# design4A.net
KiCad netlist of a schematic drawn in EAGLE
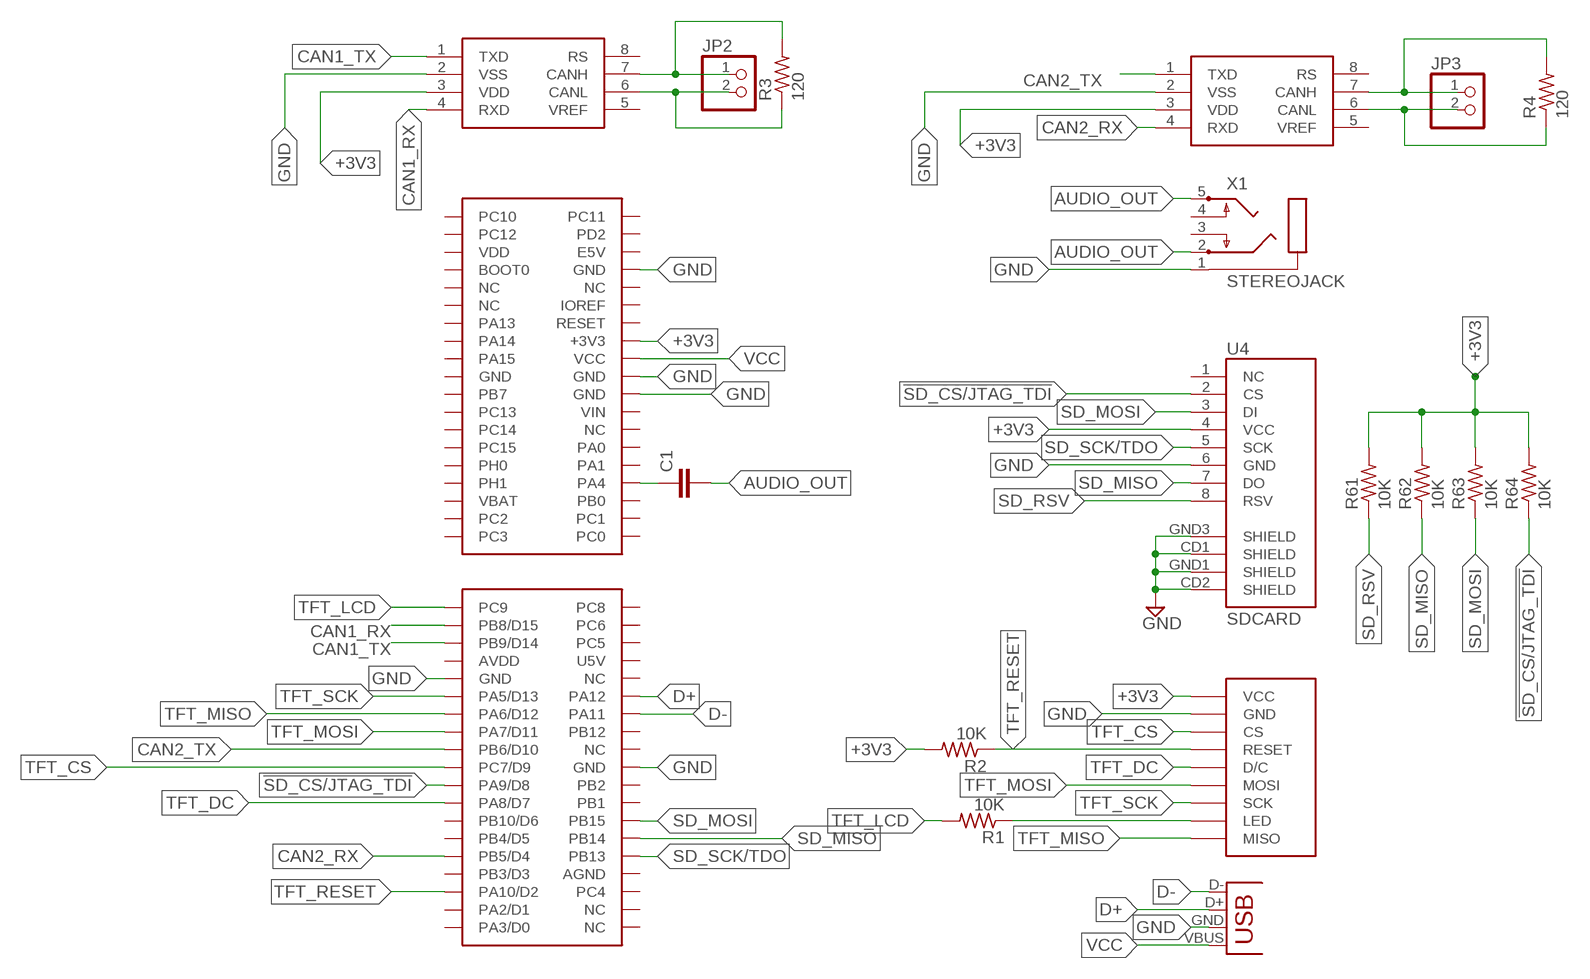
[diagram p0: schematic, sheet 1]

(export (version "E")
  (design (tool "Eeschema 10.0.6"))
  (components
    (comp (ref "C1")
      (value "CAP1206")
      (footprint "eagle-import:1206")
      (libsource (lib "eagle-import") (part "CAP1206"))
    )
    (comp (ref "J1")
      (value "SPI_TFT_DISPLAY")
      (footprint "eagle-import:SPI_DISPLAY")
      (libsource (lib "eagle-import") (part "SPI_TFT_DISPLAY"))
    )
    (comp (ref "JP1")
      (value "USB-A-H")
      (footprint "eagle-import:USB-A-H")
      (libsource (lib "eagle-import") (part "USB-A-H"))
    )
    (comp (ref "JP2")
      (value "HEADER-1X2")
      (footprint "eagle-import:1X02_OVAL")
      (libsource (lib "eagle-import") (part "HEADER-1X2"))
    )
    (comp (ref "JP3")
      (value "HEADER-1X2")
      (footprint "eagle-import:1X02_OVAL")
      (libsource (lib "eagle-import") (part "HEADER-1X2"))
    )
    (comp (ref "R1")
      (value "10K")
      (footprint "eagle-import:RLC_0603@1")
      (fields (field (name "MPN") "RMCF0603JT10K0"))
      (libsource (lib "eagle-import") (part "RESISTORRLC_0603"))
    )
    (comp (ref "R2")
      (value "10K")
      (footprint "eagle-import:RLC_0603@1")
      (fields (field (name "MPN") "RMCF0603JT10K0"))
      (libsource (lib "eagle-import") (part "RESISTORRLC_0603"))
    )
    (comp (ref "R3")
      (value "120")
      (footprint "eagle-import:RLC_0603@1")
      (fields (field (name "MPN") "RMCF0603JT10K0"))
      (libsource (lib "eagle-import") (part "RESISTORRLC_0603"))
    )
    (comp (ref "R4")
      (value "120")
      (footprint "eagle-import:RLC_0603@1")
      (fields (field (name "MPN") "RMCF0603JT10K0"))
      (libsource (lib "eagle-import") (part "RESISTORRLC_0603"))
    )
    (comp (ref "R61")
      (value "10K")
      (footprint "eagle-import:RLC_0603@1")
      (fields (field (name "MPN") "RMCF0603JT10K0"))
      (libsource (lib "eagle-import") (part "RESISTORRLC_0603"))
    )
    (comp (ref "R62")
      (value "10K")
      (footprint "eagle-import:RLC_0603@1")
      (fields (field (name "MPN") "RMCF0603JT10K0"))
      (libsource (lib "eagle-import") (part "RESISTORRLC_0603"))
    )
    (comp (ref "R63")
      (value "10K")
      (footprint "eagle-import:RLC_0603@1")
      (fields (field (name "MPN") "RMCF0603JT10K0"))
      (libsource (lib "eagle-import") (part "RESISTORRLC_0603"))
    )
    (comp (ref "R64")
      (value "10K")
      (footprint "eagle-import:RLC_0603@1")
      (fields (field (name "MPN") "RMCF0603JT10K0"))
      (libsource (lib "eagle-import") (part "RESISTORRLC_0603"))
    )
    (comp (ref "U$1")
      (value "MOPHOMOPHO_466RE")
      (footprint "eagle-import:MOPHO")
      (libsource (lib "eagle-import") (part "MOPHOMOPHO_466RE"))
    )
    (comp (ref "U1")
      (value "MCP2551")
      (footprint "eagle-import:SO08")
      (libsource (lib "eagle-import") (part "MCP2551"))
    )
    (comp (ref "U2")
      (value "MCP2551")
      (footprint "eagle-import:SO08")
      (libsource (lib "eagle-import") (part "MCP2551"))
    )
    (comp (ref "U4")
      (value "SDCARD")
      (footprint "eagle-import:MICRO-SD-SOCKET-PP")
      (libsource (lib "eagle-import") (part "USD-SOCKETNEW"))
    )
    (comp (ref "X1")
      (value "STEREOJACK")
      (footprint "eagle-import:STX3100")
      (libsource (lib "eagle-import") (part "STEREOJACK"))
    )
  )
  (nets
    (net (code "1") (name "+3V3") (class "Default")
      (node (ref "J1") (pin "VCC") (pinfunction "VCC_VCC") (pintype "power_in"))
      (node (ref "R2") (pin "2") (pinfunction "2_2") (pintype "passive"))
      (node (ref "R61") (pin "2") (pinfunction "2_2") (pintype "passive"))
      (node (ref "R62") (pin "2") (pinfunction "2_2") (pintype "passive"))
      (node (ref "R63") (pin "2") (pinfunction "2_2") (pintype "passive"))
      (node (ref "R64") (pin "2") (pinfunction "2_2") (pintype "passive"))
      (node (ref "U$1") (pin "P$16") (pinfunction "+3V3_P$16") (pintype "power_in"))
      (node (ref "U1") (pin "3") (pinfunction "VDD_3") (pintype "bidirectional"))
      (node (ref "U2") (pin "3") (pinfunction "VDD_3") (pintype "bidirectional"))
      (node (ref "U4") (pin "4") (pinfunction "VCC_4") (pintype "bidirectional"))
    )
    (net (code "2") (name "/AVDD") (class "Default")
      (node (ref "U$1") (pin "P$45") (pinfunction "AVDD_P$45") (pintype "power_in"))
    )
    (net (code "3") (name "/VBAT") (class "Default")
      (node (ref "U$1") (pin "P$33") (pinfunction "VBAT_P$33") (pintype "power_in"))
    )
    (net (code "4") (name "/VDD") (class "Default")
      (node (ref "U$1") (pin "P$5") (pinfunction "VDD_P$5") (pintype "power_in"))
    )
    (net (code "5") (name "/VIN") (class "Default")
      (node (ref "U$1") (pin "P$24") (pinfunction "VIN_P$24") (pintype "power_in"))
    )
    (net (code "6") (name "/~{SD_CS{slash}JTAG_TDI}") (class "Default")
      (node (ref "R64") (pin "1") (pinfunction "1_1") (pintype "passive"))
      (node (ref "U$1") (pin "P$59") (pinfunction "PA9/D8_P$59") (pintype "bidirectional"))
      (node (ref "U4") (pin "2") (pinfunction "CS_2") (pintype "bidirectional"))
    )
    (net (code "7") (name "AUDIO_OUT") (class "Default")
      (node (ref "C1") (pin "2") (pinfunction "2_2") (pintype "passive"))
      (node (ref "X1") (pin "2") (pinfunction "2_2") (pintype "passive"))
      (node (ref "X1") (pin "5") (pinfunction "5_5") (pintype "passive"))
    )
    (net (code "8") (name "CAN1_RX") (class "Default")
      (node (ref "U$1") (pin "P$41") (pinfunction "PB8/D15_P$41") (pintype "bidirectional"))
      (node (ref "U2") (pin "4") (pinfunction "RXD_4") (pintype "bidirectional"))
    )
    (net (code "9") (name "CAN1_TX") (class "Default")
      (node (ref "U$1") (pin "P$43") (pinfunction "PB9/D14_P$43") (pintype "bidirectional"))
      (node (ref "U2") (pin "1") (pinfunction "TXD_1") (pintype "bidirectional"))
    )
    (net (code "10") (name "CAN2_RX") (class "Default")
      (node (ref "U$1") (pin "P$67") (pinfunction "PB5/D4_P$67") (pintype "bidirectional"))
      (node (ref "U1") (pin "4") (pinfunction "RXD_4") (pintype "bidirectional"))
    )
    (net (code "11") (name "CAN2_TX") (class "Default")
      (node (ref "U$1") (pin "P$55") (pinfunction "PB6/D10_P$55") (pintype "bidirectional"))
      (node (ref "U1") (pin "1") (pinfunction "TXD_1") (pintype "bidirectional"))
    )
    (net (code "12") (name "D+") (class "Default")
      (node (ref "JP1") (pin "D+") (pinfunction "D-_D+") (pintype "bidirectional"))
      (node (ref "U$1") (pin "P$50") (pinfunction "PA12_P$50") (pintype "bidirectional"))
    )
    (net (code "13") (name "D-") (class "Default")
      (node (ref "JP1") (pin "D-") (pinfunction "D+_D-") (pintype "bidirectional"))
      (node (ref "U$1") (pin "P$52") (pinfunction "PA11_P$52") (pintype "bidirectional"))
    )
    (net (code "14") (name "GND") (class "Default")
      (node (ref "J1") (pin "GND") (pinfunction "GND_GND") (pintype "power_in"))
      (node (ref "JP1") (pin "GND") (pinfunction "VBUS_GND") (pintype "bidirectional"))
      (node (ref "U$1") (pin "P$20") (pinfunction "GND_P$20") (pintype "bidirectional"))
      (node (ref "U$1") (pin "P$22") (pinfunction "GND_P$22") (pintype "bidirectional"))
      (node (ref "U$1") (pin "P$47") (pinfunction "GND_P$47") (pintype "bidirectional"))
      (node (ref "U$1") (pin "P$58") (pinfunction "GND_P$58") (pintype "bidirectional"))
      (node (ref "U$1") (pin "P$8") (pinfunction "GND_P$8") (pintype "bidirectional"))
      (node (ref "U1") (pin "2") (pinfunction "VSS_2") (pintype "bidirectional"))
      (node (ref "U2") (pin "2") (pinfunction "VSS_2") (pintype "bidirectional"))
      (node (ref "U4") (pin "6") (pinfunction "GND_6") (pintype "bidirectional"))
      (node (ref "U4") (pin "CD1") (pinfunction "SHIELD_CD1") (pintype "bidirectional"))
      (node (ref "U4") (pin "CD2") (pinfunction "SHIELD_CD2") (pintype "bidirectional"))
      (node (ref "U4") (pin "GND1") (pinfunction "SHIELD_GND1") (pintype "bidirectional"))
      (node (ref "U4") (pin "GND3") (pinfunction "SHIELD_GND3") (pintype "bidirectional"))
      (node (ref "X1") (pin "1") (pinfunction "1_1") (pintype "passive"))
    )
    (net (code "15") (name "Net-(J1-PadLED)") (class "Default")
      (node (ref "J1") (pin "LED") (pinfunction "LED_LED") (pintype "bidirectional"))
      (node (ref "R1") (pin "1") (pinfunction "1_1") (pintype "passive"))
    )
    (net (code "16") (name "Net-(U$1-PA4)") (class "Default")
      (node (ref "C1") (pin "1") (pinfunction "1_1") (pintype "passive"))
      (node (ref "U$1") (pin "P$32") (pinfunction "PA4_P$32") (pintype "bidirectional"))
    )
    (net (code "17") (name "Net-(U1-CANH)") (class "Default")
      (node (ref "JP3") (pin "1") (pinfunction "1_1") (pintype "passive"))
      (node (ref "R4") (pin "2") (pinfunction "2_2") (pintype "passive"))
      (node (ref "U1") (pin "7") (pinfunction "CANH_7") (pintype "bidirectional"))
    )
    (net (code "18") (name "Net-(U1-CANL)") (class "Default")
      (node (ref "JP3") (pin "2") (pinfunction "2_2") (pintype "passive"))
      (node (ref "R4") (pin "1") (pinfunction "1_1") (pintype "passive"))
      (node (ref "U1") (pin "6") (pinfunction "CANL_6") (pintype "bidirectional"))
    )
    (net (code "19") (name "Net-(U2-CANH)") (class "Default")
      (node (ref "JP2") (pin "1") (pinfunction "1_1") (pintype "passive"))
      (node (ref "R3") (pin "2") (pinfunction "2_2") (pintype "passive"))
      (node (ref "U2") (pin "7") (pinfunction "CANH_7") (pintype "bidirectional"))
    )
    (net (code "20") (name "Net-(U2-CANL)") (class "Default")
      (node (ref "JP2") (pin "2") (pinfunction "2_2") (pintype "passive"))
      (node (ref "R3") (pin "1") (pinfunction "1_1") (pintype "passive"))
      (node (ref "U2") (pin "6") (pinfunction "CANL_6") (pintype "bidirectional"))
    )
    (net (code "21") (name "SD_MISO") (class "Default")
      (node (ref "R62") (pin "1") (pinfunction "1_1") (pintype "passive"))
      (node (ref "U$1") (pin "P$66") (pinfunction "PB14_P$66") (pintype "bidirectional"))
      (node (ref "U4") (pin "7") (pinfunction "DO_7") (pintype "bidirectional"))
    )
    (net (code "22") (name "SD_MOSI") (class "Default")
      (node (ref "R63") (pin "1") (pinfunction "1_1") (pintype "passive"))
      (node (ref "U$1") (pin "P$64") (pinfunction "PB15_P$64") (pintype "bidirectional"))
      (node (ref "U4") (pin "3") (pinfunction "DI_3") (pintype "bidirectional"))
    )
    (net (code "23") (name "SD_RSV") (class "Default")
      (node (ref "R61") (pin "1") (pinfunction "1_1") (pintype "passive"))
      (node (ref "U4") (pin "8") (pinfunction "RSV_8") (pintype "bidirectional"))
    )
    (net (code "24") (name "SD_SCK{slash}TDO") (class "Default")
      (node (ref "U$1") (pin "P$68") (pinfunction "PB13_P$68") (pintype "bidirectional"))
      (node (ref "U4") (pin "5") (pinfunction "SCK_5") (pintype "bidirectional"))
    )
    (net (code "25") (name "TFT_CS") (class "Default")
      (node (ref "J1") (pin "CS") (pinfunction "CS_CS") (pintype "bidirectional"))
      (node (ref "U$1") (pin "P$57") (pinfunction "PC7/D9_P$57") (pintype "bidirectional"))
    )
    (net (code "26") (name "TFT_DC") (class "Default")
      (node (ref "J1") (pin "D/C") (pinfunction "D/C_D/C") (pintype "bidirectional"))
      (node (ref "U$1") (pin "P$61") (pinfunction "PA8/D7_P$61") (pintype "bidirectional"))
    )
    (net (code "27") (name "TFT_LCD") (class "Default")
      (node (ref "R1") (pin "2") (pinfunction "2_2") (pintype "passive"))
      (node (ref "U$1") (pin "P$39") (pinfunction "PC9_P$39") (pintype "bidirectional"))
    )
    (net (code "28") (name "TFT_MISO") (class "Default")
      (node (ref "J1") (pin "MISO") (pinfunction "MISO_MISO") (pintype "bidirectional"))
      (node (ref "U$1") (pin "P$51") (pinfunction "PA6/D12_P$51") (pintype "bidirectional"))
    )
    (net (code "29") (name "TFT_MOSI") (class "Default")
      (node (ref "J1") (pin "MOSI") (pinfunction "MOSI_MOSI") (pintype "bidirectional"))
      (node (ref "U$1") (pin "P$53") (pinfunction "PA7/D11_P$53") (pintype "bidirectional"))
    )
    (net (code "30") (name "TFT_RESET") (class "Default")
      (node (ref "J1") (pin "RESET") (pinfunction "RESET_RESET") (pintype "bidirectional"))
      (node (ref "R2") (pin "1") (pinfunction "1_1") (pintype "passive"))
      (node (ref "U$1") (pin "P$71") (pinfunction "PA10/D2_P$71") (pintype "bidirectional"))
    )
    (net (code "31") (name "TFT_SCK") (class "Default")
      (node (ref "J1") (pin "SCK") (pinfunction "SCK_SCK") (pintype "bidirectional"))
      (node (ref "U$1") (pin "P$49") (pinfunction "PA5/D13_P$49") (pintype "bidirectional"))
    )
    (net (code "32") (name "VCC") (class "Default")
      (node (ref "JP1") (pin "VBUS") (pinfunction "GND_VBUS") (pintype "bidirectional"))
      (node (ref "U$1") (pin "P$18") (pinfunction "VCC_P$18") (pintype "power_in"))
    )
    (net (code "33") (name "unconnected-(U$1-AGND-PadP$70)") (class "Default")
      (node (ref "U$1") (pin "P$70") (pinfunction "AGND_P$70") (pintype "bidirectional"))
    )
    (net (code "34") (name "unconnected-(U$1-BOOT0-PadP$7)") (class "Default")
      (node (ref "U$1") (pin "P$7") (pinfunction "BOOT0_P$7") (pintype "bidirectional"))
    )
    (net (code "35") (name "unconnected-(U$1-E5V-PadP$6)") (class "Default")
      (node (ref "U$1") (pin "P$6") (pinfunction "E5V_P$6") (pintype "bidirectional"))
    )
    (net (code "36") (name "unconnected-(U$1-GND-PadP$19)") (class "Default")
      (node (ref "U$1") (pin "P$19") (pinfunction "GND_P$19") (pintype "bidirectional"))
    )
    (net (code "37") (name "unconnected-(U$1-IOREF-PadP$12)") (class "Default")
      (node (ref "U$1") (pin "P$12") (pinfunction "IOREF_P$12") (pintype "bidirectional"))
    )
    (net (code "38") (name "unconnected-(U$1-NC-PadP$9)") (class "Default")
      (node (ref "U$1") (pin "P$9") (pinfunction "NC_P$9") (pintype "bidirectional"))
    )
    (net (code "39") (name "unconnected-(U$1-NC-PadP$10)") (class "Default")
      (node (ref "U$1") (pin "P$10") (pinfunction "NC_P$10") (pintype "bidirectional"))
    )
    (net (code "40") (name "unconnected-(U$1-NC-PadP$11)") (class "Default")
      (node (ref "U$1") (pin "P$11") (pinfunction "NC_P$11") (pintype "bidirectional"))
    )
    (net (code "41") (name "unconnected-(U$1-NC-PadP$26)") (class "Default")
      (node (ref "U$1") (pin "P$26") (pinfunction "NC_P$26") (pintype "bidirectional"))
    )
    (net (code "42") (name "unconnected-(U$1-NC-PadP$48)") (class "Default")
      (node (ref "U$1") (pin "P$48") (pinfunction "NC_P$48") (pintype "bidirectional"))
    )
    (net (code "43") (name "unconnected-(U$1-NC-PadP$56)") (class "Default")
      (node (ref "U$1") (pin "P$56") (pinfunction "NC_P$56") (pintype "bidirectional"))
    )
    (net (code "44") (name "unconnected-(U$1-NC-PadP$74)") (class "Default")
      (node (ref "U$1") (pin "P$74") (pinfunction "NC_P$74") (pintype "bidirectional"))
    )
    (net (code "45") (name "unconnected-(U$1-NC-PadP$76)") (class "Default")
      (node (ref "U$1") (pin "P$76") (pinfunction "NC_P$76") (pintype "bidirectional"))
    )
    (net (code "46") (name "unconnected-(U$1-PA0-PadP$28)") (class "Default")
      (node (ref "U$1") (pin "P$28") (pinfunction "PA0_P$28") (pintype "bidirectional"))
    )
    (net (code "47") (name "unconnected-(U$1-PA1-PadP$30)") (class "Default")
      (node (ref "U$1") (pin "P$30") (pinfunction "PA1_P$30") (pintype "bidirectional"))
    )
    (net (code "48") (name "unconnected-(U$1-PA2{slash}D1-PadP$73)") (class "Default")
      (node (ref "U$1") (pin "P$73") (pinfunction "PA2/D1_P$73") (pintype "bidirectional"))
    )
    (net (code "49") (name "unconnected-(U$1-PA3{slash}D0-PadP$75)") (class "Default")
      (node (ref "U$1") (pin "P$75") (pinfunction "PA3/D0_P$75") (pintype "bidirectional"))
    )
    (net (code "50") (name "unconnected-(U$1-PA13-PadP$13)") (class "Default")
      (node (ref "U$1") (pin "P$13") (pinfunction "PA13_P$13") (pintype "bidirectional"))
    )
    (net (code "51") (name "unconnected-(U$1-PA14-PadP$15)") (class "Default")
      (node (ref "U$1") (pin "P$15") (pinfunction "PA14_P$15") (pintype "bidirectional"))
    )
    (net (code "52") (name "unconnected-(U$1-PA15-PadP$17)") (class "Default")
      (node (ref "U$1") (pin "P$17") (pinfunction "PA15_P$17") (pintype "bidirectional"))
    )
    (net (code "53") (name "unconnected-(U$1-PB0-PadP$34)") (class "Default")
      (node (ref "U$1") (pin "P$34") (pinfunction "PB0_P$34") (pintype "bidirectional"))
    )
    (net (code "54") (name "unconnected-(U$1-PB1-PadP$62)") (class "Default")
      (node (ref "U$1") (pin "P$62") (pinfunction "PB1_P$62") (pintype "bidirectional"))
    )
    (net (code "55") (name "unconnected-(U$1-PB2-PadP$60)") (class "Default")
      (node (ref "U$1") (pin "P$60") (pinfunction "PB2_P$60") (pintype "bidirectional"))
    )
    (net (code "56") (name "unconnected-(U$1-PB3{slash}D3-PadP$69)") (class "Default")
      (node (ref "U$1") (pin "P$69") (pinfunction "PB3/D3_P$69") (pintype "bidirectional"))
    )
    (net (code "57") (name "unconnected-(U$1-PB4{slash}D5-PadP$65)") (class "Default")
      (node (ref "U$1") (pin "P$65") (pinfunction "PB4/D5_P$65") (pintype "bidirectional"))
    )
    (net (code "58") (name "unconnected-(U$1-PB7-PadP$21)") (class "Default")
      (node (ref "U$1") (pin "P$21") (pinfunction "PB7_P$21") (pintype "bidirectional"))
    )
    (net (code "59") (name "unconnected-(U$1-PB10{slash}D6-PadP$63)") (class "Default")
      (node (ref "U$1") (pin "P$63") (pinfunction "PB10/D6_P$63") (pintype "bidirectional"))
    )
    (net (code "60") (name "unconnected-(U$1-PB12-PadP$54)") (class "Default")
      (node (ref "U$1") (pin "P$54") (pinfunction "PB12_P$54") (pintype "bidirectional"))
    )
    (net (code "61") (name "unconnected-(U$1-PC0-PadP$38)") (class "Default")
      (node (ref "U$1") (pin "P$38") (pinfunction "PC0_P$38") (pintype "bidirectional"))
    )
    (net (code "62") (name "unconnected-(U$1-PC1-PadP$36)") (class "Default")
      (node (ref "U$1") (pin "P$36") (pinfunction "PC1_P$36") (pintype "bidirectional"))
    )
    (net (code "63") (name "unconnected-(U$1-PC2-PadP$35)") (class "Default")
      (node (ref "U$1") (pin "P$35") (pinfunction "PC2_P$35") (pintype "bidirectional"))
    )
    (net (code "64") (name "unconnected-(U$1-PC3-PadP$37)") (class "Default")
      (node (ref "U$1") (pin "P$37") (pinfunction "PC3_P$37") (pintype "bidirectional"))
    )
    (net (code "65") (name "unconnected-(U$1-PC4-PadP$72)") (class "Default")
      (node (ref "U$1") (pin "P$72") (pinfunction "PC4_P$72") (pintype "bidirectional"))
    )
    (net (code "66") (name "unconnected-(U$1-PC5-PadP$44)") (class "Default")
      (node (ref "U$1") (pin "P$44") (pinfunction "PC5_P$44") (pintype "bidirectional"))
    )
    (net (code "67") (name "unconnected-(U$1-PC6-PadP$42)") (class "Default")
      (node (ref "U$1") (pin "P$42") (pinfunction "PC6_P$42") (pintype "bidirectional"))
    )
    (net (code "68") (name "unconnected-(U$1-PC8-PadP$40)") (class "Default")
      (node (ref "U$1") (pin "P$40") (pinfunction "PC8_P$40") (pintype "bidirectional"))
    )
    (net (code "69") (name "unconnected-(U$1-PC10-PadP$1)") (class "Default")
      (node (ref "U$1") (pin "P$1") (pinfunction "PC10_P$1") (pintype "bidirectional"))
    )
    (net (code "70") (name "unconnected-(U$1-PC11-PadP$2)") (class "Default")
      (node (ref "U$1") (pin "P$2") (pinfunction "PC11_P$2") (pintype "bidirectional"))
    )
    (net (code "71") (name "unconnected-(U$1-PC12-PadP$3)") (class "Default")
      (node (ref "U$1") (pin "P$3") (pinfunction "PC12_P$3") (pintype "bidirectional"))
    )
    (net (code "72") (name "unconnected-(U$1-PC13-PadP$23)") (class "Default")
      (node (ref "U$1") (pin "P$23") (pinfunction "PC13_P$23") (pintype "bidirectional"))
    )
    (net (code "73") (name "unconnected-(U$1-PC14-PadP$25)") (class "Default")
      (node (ref "U$1") (pin "P$25") (pinfunction "PC14_P$25") (pintype "bidirectional"))
    )
    (net (code "74") (name "unconnected-(U$1-PC15-PadP$27)") (class "Default")
      (node (ref "U$1") (pin "P$27") (pinfunction "PC15_P$27") (pintype "bidirectional"))
    )
    (net (code "75") (name "unconnected-(U$1-PD2-PadP$4)") (class "Default")
      (node (ref "U$1") (pin "P$4") (pinfunction "PD2_P$4") (pintype "bidirectional"))
    )
    (net (code "76") (name "unconnected-(U$1-PH0-PadP$29)") (class "Default")
      (node (ref "U$1") (pin "P$29") (pinfunction "PH0_P$29") (pintype "bidirectional"))
    )
    (net (code "77") (name "unconnected-(U$1-PH1-PadP$31)") (class "Default")
      (node (ref "U$1") (pin "P$31") (pinfunction "PH1_P$31") (pintype "bidirectional"))
    )
    (net (code "78") (name "unconnected-(U$1-RESET-PadP$14)") (class "Default")
      (node (ref "U$1") (pin "P$14") (pinfunction "RESET_P$14") (pintype "bidirectional"))
    )
    (net (code "79") (name "unconnected-(U$1-U5V-PadP$46)") (class "Default")
      (node (ref "U$1") (pin "P$46") (pinfunction "U5V_P$46") (pintype "bidirectional"))
    )
    (net (code "80") (name "unconnected-(U1-RS-Pad8)") (class "Default")
      (node (ref "U1") (pin "8") (pinfunction "RS_8") (pintype "bidirectional"))
    )
    (net (code "81") (name "unconnected-(U1-VREF-Pad5)") (class "Default")
      (node (ref "U1") (pin "5") (pinfunction "VREF_5") (pintype "bidirectional"))
    )
    (net (code "82") (name "unconnected-(U2-RS-Pad8)") (class "Default")
      (node (ref "U2") (pin "8") (pinfunction "RS_8") (pintype "bidirectional"))
    )
    (net (code "83") (name "unconnected-(U2-VREF-Pad5)") (class "Default")
      (node (ref "U2") (pin "5") (pinfunction "VREF_5") (pintype "bidirectional"))
    )
    (net (code "84") (name "unconnected-(U4-NC-Pad1)") (class "Default")
      (node (ref "U4") (pin "1") (pinfunction "NC_1") (pintype "bidirectional"))
    )
    (net (code "85") (name "unconnected-(X1-Pad3)") (class "Default")
      (node (ref "X1") (pin "3") (pinfunction "3_3") (pintype "passive"))
    )
    (net (code "86") (name "unconnected-(X1-Pad4)") (class "Default")
      (node (ref "X1") (pin "4") (pinfunction "4_4") (pintype "passive"))
    )
  )
)
